# main.net
KiCad netlist of a schematic drawn in EAGLE
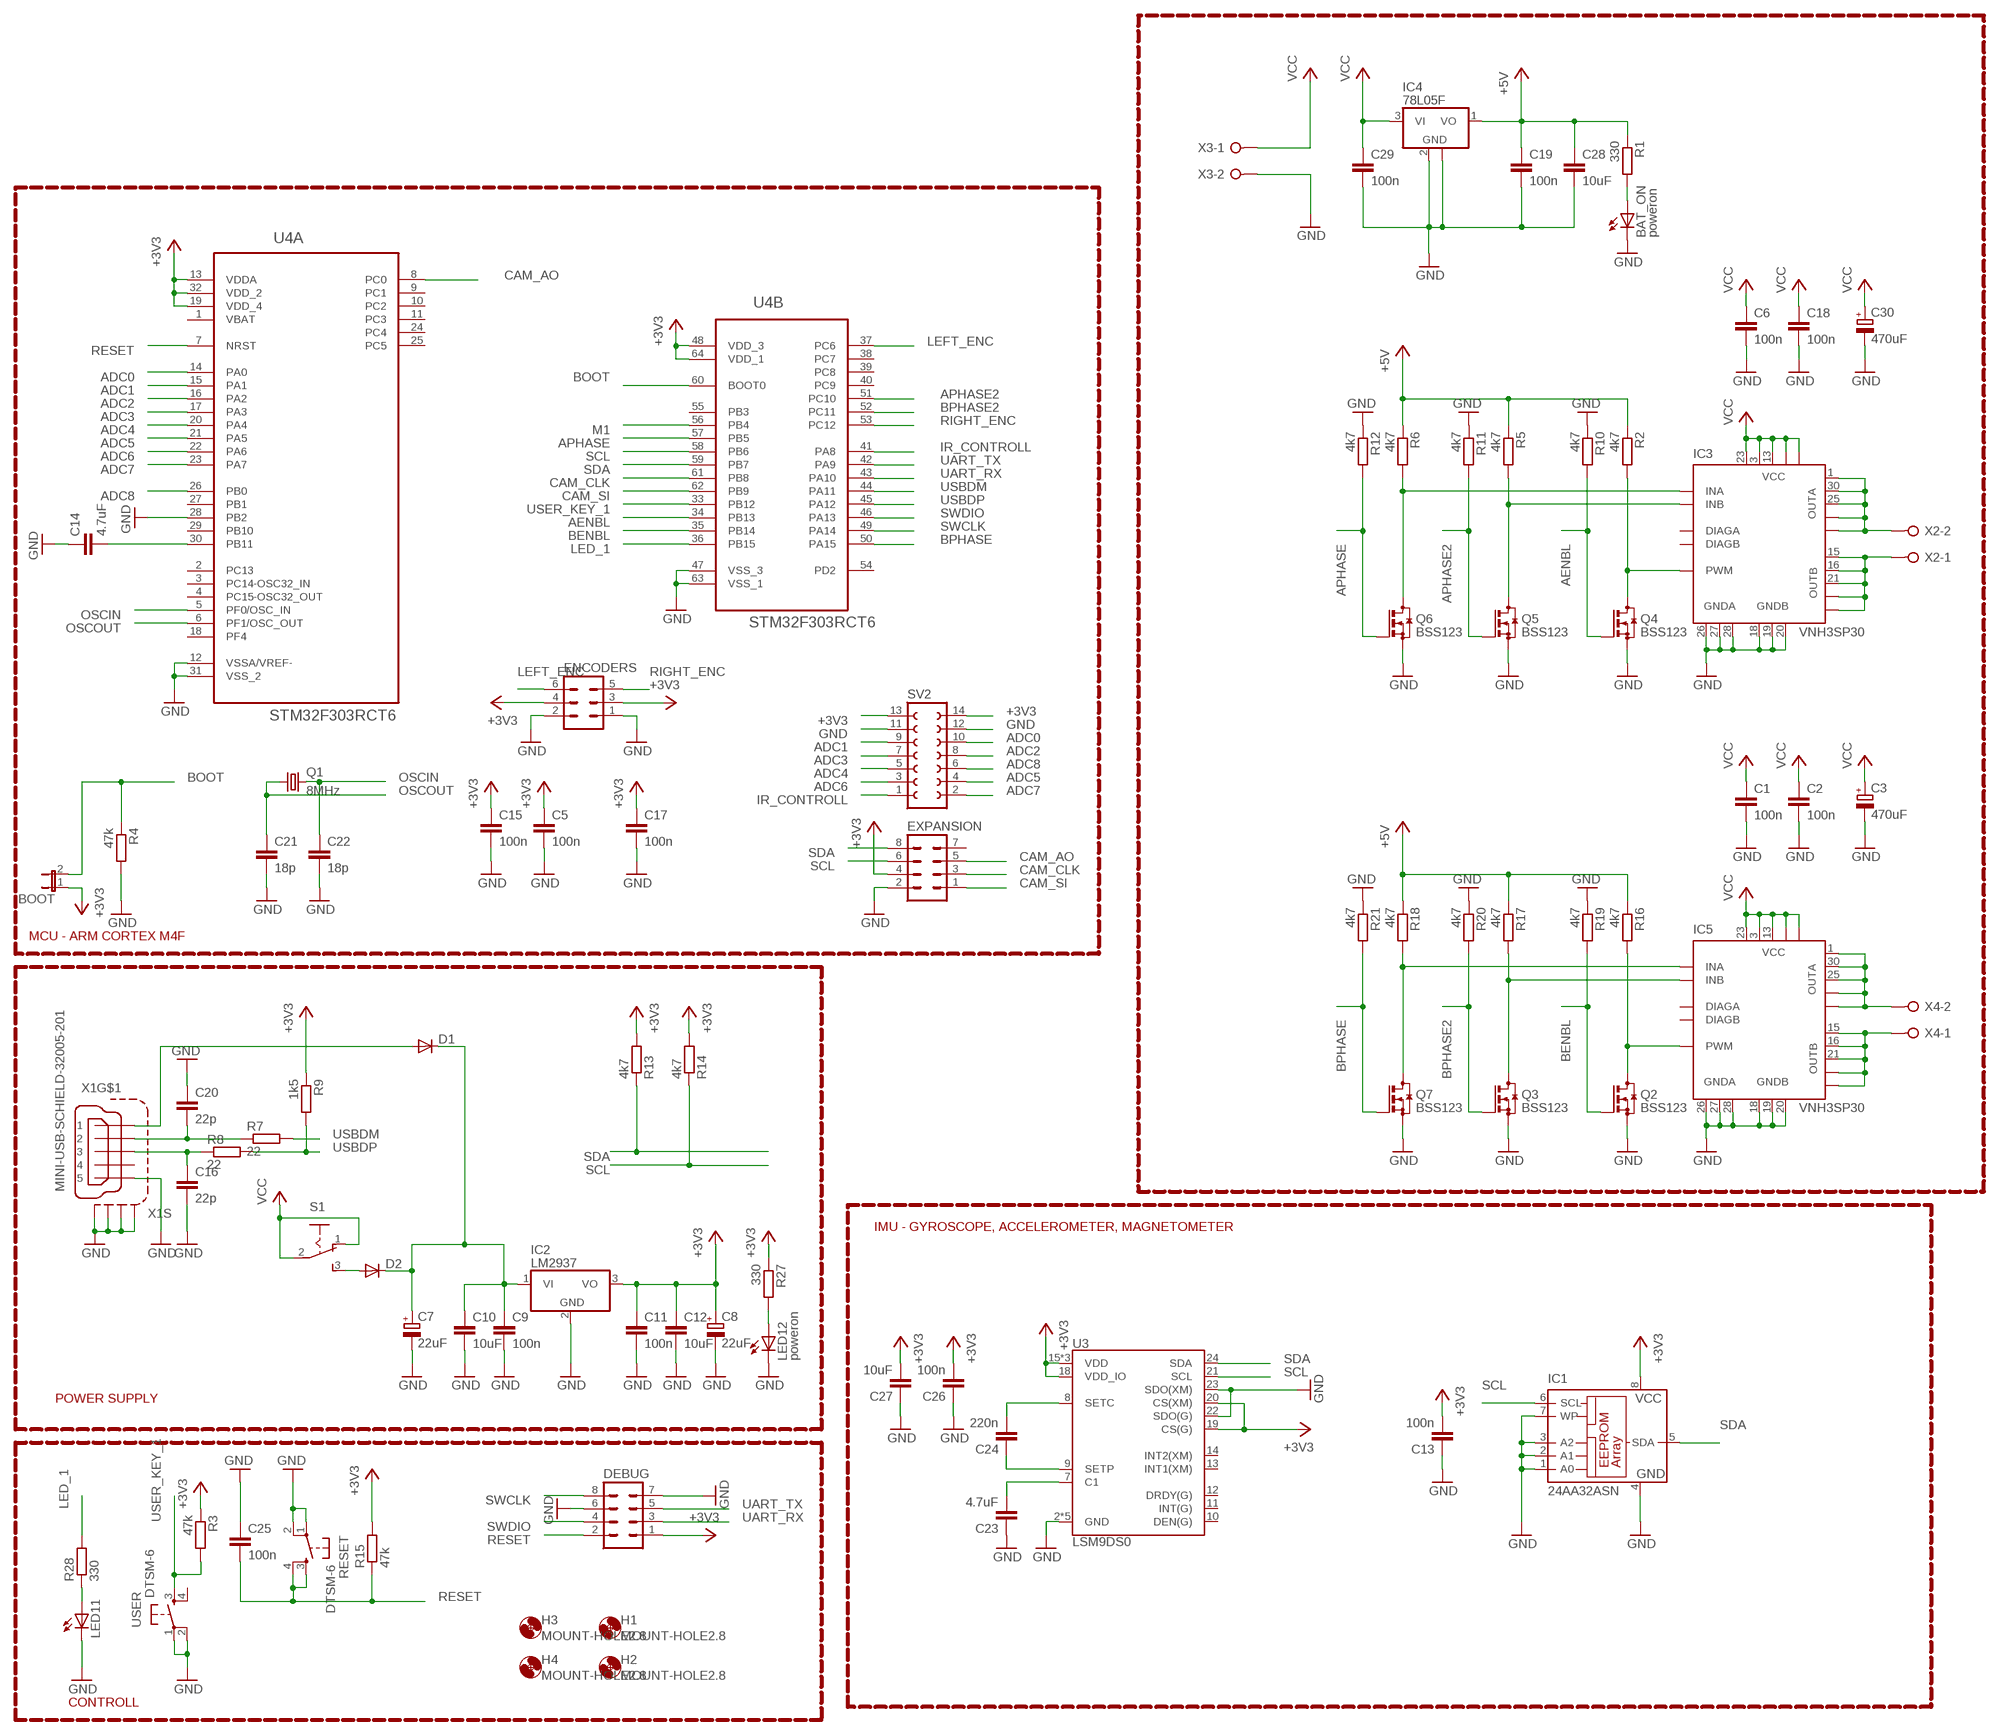
[diagram p0: schematic, sheet 1]

(export (version "E")
  (design (tool "Eeschema 10.0.6"))
  (components
    (comp (ref "BAT_ON")
      (value "poweron")
      (footprint "eagle-import:CHIPLED_1206")
      (libsource (lib "eagle-import") (part "LEDCHIPLED_1206"))
    )
    (comp (ref "BOOT")
      (value "JP1E")
      (footprint "eagle-import:JP1")
      (libsource (lib "eagle-import") (part "JP1E"))
    )
    (comp (ref "C1")
      (value "100n")
      (footprint "eagle-import:C0805")
      (libsource (lib "eagle-import") (part "C-EUC0805"))
    )
    (comp (ref "C2")
      (value "100n")
      (footprint "eagle-import:C0805")
      (libsource (lib "eagle-import") (part "C-EUC0805"))
    )
    (comp (ref "C3")
      (value "470uF")
      (footprint "eagle-import:140CLH-1014")
      (libsource (lib "eagle-import") (part "CPOL-EU140CLH-1014"))
    )
    (comp (ref "C5")
      (value "100n")
      (footprint "eagle-import:C0805")
      (libsource (lib "eagle-import") (part "C-EUC0805"))
    )
    (comp (ref "C6")
      (value "100n")
      (footprint "eagle-import:C0805")
      (libsource (lib "eagle-import") (part "C-EUC0805"))
    )
    (comp (ref "C7")
      (value "22uF")
      (footprint "eagle-import:153CLV-0505")
      (libsource (lib "eagle-import") (part "CPOL-EU153CLV-0505"))
    )
    (comp (ref "C8")
      (value "22uF")
      (footprint "eagle-import:153CLV-0505")
      (libsource (lib "eagle-import") (part "CPOL-EU153CLV-0505"))
    )
    (comp (ref "C9")
      (value "100n")
      (footprint "eagle-import:C0805")
      (libsource (lib "eagle-import") (part "C-EUC0805"))
    )
    (comp (ref "C10")
      (value "10uF")
      (footprint "eagle-import:C0805")
      (libsource (lib "eagle-import") (part "C-EUC0805"))
    )
    (comp (ref "C11")
      (value "100n")
      (footprint "eagle-import:C0805")
      (libsource (lib "eagle-import") (part "C-EUC0805"))
    )
    (comp (ref "C12")
      (value "10uF")
      (footprint "eagle-import:C0805")
      (libsource (lib "eagle-import") (part "C-EUC0805"))
    )
    (comp (ref "C13")
      (value "100n")
      (footprint "eagle-import:C0805")
      (libsource (lib "eagle-import") (part "C-EUC0805"))
    )
    (comp (ref "C14")
      (value "4.7uF")
      (footprint "eagle-import:C0805")
      (libsource (lib "eagle-import") (part "C-EUC0805"))
    )
    (comp (ref "C15")
      (value "100n")
      (footprint "eagle-import:C0805")
      (libsource (lib "eagle-import") (part "C-EUC0805"))
    )
    (comp (ref "C16")
      (value "22p")
      (footprint "eagle-import:C0805")
      (libsource (lib "eagle-import") (part "C-EUC0805"))
    )
    (comp (ref "C17")
      (value "100n")
      (footprint "eagle-import:C0805")
      (libsource (lib "eagle-import") (part "C-EUC0805"))
    )
    (comp (ref "C18")
      (value "100n")
      (footprint "eagle-import:C0805")
      (libsource (lib "eagle-import") (part "C-EUC0805"))
    )
    (comp (ref "C19")
      (value "100n")
      (footprint "eagle-import:C0805")
      (libsource (lib "eagle-import") (part "C-EUC0805"))
    )
    (comp (ref "C20")
      (value "22p")
      (footprint "eagle-import:C0805")
      (libsource (lib "eagle-import") (part "C-EUC0805"))
    )
    (comp (ref "C21")
      (value "18p")
      (footprint "eagle-import:C0805")
      (libsource (lib "eagle-import") (part "C-EUC0805"))
    )
    (comp (ref "C22")
      (value "18p")
      (footprint "eagle-import:C0805")
      (libsource (lib "eagle-import") (part "C-EUC0805"))
    )
    (comp (ref "C23")
      (value "4.7uF")
      (footprint "eagle-import:C0805")
      (libsource (lib "eagle-import") (part "C-EUC0805"))
    )
    (comp (ref "C24")
      (value "220n")
      (footprint "eagle-import:C0805")
      (libsource (lib "eagle-import") (part "C-EUC0805"))
    )
    (comp (ref "C25")
      (value "100n")
      (footprint "eagle-import:C0805")
      (libsource (lib "eagle-import") (part "C-EUC0805"))
    )
    (comp (ref "C26")
      (value "100n")
      (footprint "eagle-import:C0805")
      (libsource (lib "eagle-import") (part "C-EUC0805"))
    )
    (comp (ref "C27")
      (value "10uF")
      (footprint "eagle-import:C0805")
      (libsource (lib "eagle-import") (part "C-EUC0805"))
    )
    (comp (ref "C28")
      (value "10uF")
      (footprint "eagle-import:C0805")
      (libsource (lib "eagle-import") (part "C-EUC0805"))
    )
    (comp (ref "C29")
      (value "100n")
      (footprint "eagle-import:C0805")
      (libsource (lib "eagle-import") (part "C-EUC0805"))
    )
    (comp (ref "C30")
      (value "470uF")
      (footprint "eagle-import:140CLH-1014")
      (libsource (lib "eagle-import") (part "CPOL-EU140CLH-1014"))
    )
    (comp (ref "D1")
      (value "DIODE-SMB")
      (footprint "eagle-import:SMB")
      (libsource (lib "eagle-import") (part "DIODE-SMB"))
    )
    (comp (ref "D2")
      (value "DIODE-SMB")
      (footprint "eagle-import:SMB")
      (libsource (lib "eagle-import") (part "DIODE-SMB"))
    )
    (comp (ref "DEBUG")
      (value "MA04-2")
      (footprint "eagle-import:MA04-2")
      (libsource (lib "eagle-import") (part "MA04-2"))
    )
    (comp (ref "ENCODERS")
      (value "MA03-2")
      (footprint "eagle-import:MA03-2")
      (libsource (lib "eagle-import") (part "MA03-2"))
    )
    (comp (ref "EXPANSION")
      (value "MA04-2")
      (footprint "eagle-import:MA04-2")
      (libsource (lib "eagle-import") (part "MA04-2"))
    )
    (comp (ref "H1")
      (value "MOUNT-HOLE2.8")
      (footprint "eagle-import:2,8")
      (libsource (lib "eagle-import") (part "MOUNT-HOLE2.8"))
    )
    (comp (ref "H2")
      (value "MOUNT-HOLE2.8")
      (footprint "eagle-import:2,8")
      (libsource (lib "eagle-import") (part "MOUNT-HOLE2.8"))
    )
    (comp (ref "H3")
      (value "MOUNT-HOLE2.8")
      (footprint "eagle-import:2,8")
      (libsource (lib "eagle-import") (part "MOUNT-HOLE2.8"))
    )
    (comp (ref "H4")
      (value "MOUNT-HOLE2.8")
      (footprint "eagle-import:2,8")
      (libsource (lib "eagle-import") (part "MOUNT-HOLE2.8"))
    )
    (comp (ref "IC1")
      (value "24AA32ASN")
      (footprint "eagle-import:SO-08")
      (fields (field (name "MF") "MICROCHIP") (field (name "MPN") "24AA32A-I/SN"))
      (libsource (lib "eagle-import") (part "24SNAA32A"))
    )
    (comp (ref "IC2")
      (value "LM2937")
      (footprint "eagle-import:TO263-3")
      (libsource (lib "eagle-import") (part "LM2937"))
    )
    (comp (ref "IC3")
      (value "VNH3SP30")
      (footprint "eagle-import:MULTIPOWERSO-30")
      (fields (field (name "MPN") "VNH3SP30-E"))
      (libsource (lib "eagle-import") (part "VNH3SP30"))
    )
    (comp (ref "IC4")
      (value "78L05F")
      (footprint "eagle-import:SOT89")
      (libsource (lib "eagle-import") (part "78LF05"))
    )
    (comp (ref "IC5")
      (value "VNH3SP30")
      (footprint "eagle-import:MULTIPOWERSO-30")
      (fields (field (name "MPN") "VNH3SP30-E"))
      (libsource (lib "eagle-import") (part "VNH3SP30"))
    )
    (comp (ref "LED11")
      (value "LEDCHIPLED_1206")
      (footprint "eagle-import:CHIPLED_1206")
      (libsource (lib "eagle-import") (part "LEDCHIPLED_1206"))
    )
    (comp (ref "LED12")
      (value "poweron")
      (footprint "eagle-import:CHIPLED_1206")
      (libsource (lib "eagle-import") (part "LEDCHIPLED_1206"))
    )
    (comp (ref "Q1")
      (value "8MHz")
      (footprint "eagle-import:CTS406")
      (libsource (lib "eagle-import") (part "CRYSTALCTS406"))
    )
    (comp (ref "Q2")
      (value "BSS123")
      (footprint "eagle-import:SOT23")
      (libsource (lib "eagle-import") (part "BSS123"))
    )
    (comp (ref "Q3")
      (value "BSS123")
      (footprint "eagle-import:SOT23")
      (libsource (lib "eagle-import") (part "BSS123"))
    )
    (comp (ref "Q4")
      (value "BSS123")
      (footprint "eagle-import:SOT23")
      (libsource (lib "eagle-import") (part "BSS123"))
    )
    (comp (ref "Q5")
      (value "BSS123")
      (footprint "eagle-import:SOT23")
      (libsource (lib "eagle-import") (part "BSS123"))
    )
    (comp (ref "Q6")
      (value "BSS123")
      (footprint "eagle-import:SOT23")
      (libsource (lib "eagle-import") (part "BSS123"))
    )
    (comp (ref "Q7")
      (value "BSS123")
      (footprint "eagle-import:SOT23")
      (libsource (lib "eagle-import") (part "BSS123"))
    )
    (comp (ref "R1")
      (value "330")
      (footprint "eagle-import:M0805")
      (libsource (lib "eagle-import") (part "R-EU_M0805"))
    )
    (comp (ref "R2")
      (value "4k7")
      (footprint "eagle-import:M0805")
      (libsource (lib "eagle-import") (part "R-EU_M0805"))
    )
    (comp (ref "R3")
      (value "47k")
      (footprint "eagle-import:M0805")
      (libsource (lib "eagle-import") (part "R-EU_M0805"))
    )
    (comp (ref "R4")
      (value "47k")
      (footprint "eagle-import:M0805")
      (libsource (lib "eagle-import") (part "R-EU_M0805"))
    )
    (comp (ref "R5")
      (value "4k7")
      (footprint "eagle-import:M0805")
      (libsource (lib "eagle-import") (part "R-EU_M0805"))
    )
    (comp (ref "R6")
      (value "4k7")
      (footprint "eagle-import:M0805")
      (libsource (lib "eagle-import") (part "R-EU_M0805"))
    )
    (comp (ref "R7")
      (value "22")
      (footprint "eagle-import:M0805")
      (libsource (lib "eagle-import") (part "R-EU_M0805"))
    )
    (comp (ref "R8")
      (value "22")
      (footprint "eagle-import:M0805")
      (libsource (lib "eagle-import") (part "R-EU_M0805"))
    )
    (comp (ref "R9")
      (value "1k5")
      (footprint "eagle-import:M0805")
      (libsource (lib "eagle-import") (part "R-EU_M0805"))
    )
    (comp (ref "R10")
      (value "4k7")
      (footprint "eagle-import:M0805")
      (libsource (lib "eagle-import") (part "R-EU_M0805"))
    )
    (comp (ref "R11")
      (value "4k7")
      (footprint "eagle-import:M0805")
      (libsource (lib "eagle-import") (part "R-EU_M0805"))
    )
    (comp (ref "R12")
      (value "4k7")
      (footprint "eagle-import:M0805")
      (libsource (lib "eagle-import") (part "R-EU_M0805"))
    )
    (comp (ref "R13")
      (value "4k7")
      (footprint "eagle-import:M0805")
      (libsource (lib "eagle-import") (part "R-EU_M0805"))
    )
    (comp (ref "R14")
      (value "4k7")
      (footprint "eagle-import:M0805")
      (libsource (lib "eagle-import") (part "R-EU_M0805"))
    )
    (comp (ref "R15")
      (value "47k")
      (footprint "eagle-import:M0805")
      (libsource (lib "eagle-import") (part "R-EU_M0805"))
    )
    (comp (ref "R16")
      (value "4k7")
      (footprint "eagle-import:M0805")
      (libsource (lib "eagle-import") (part "R-EU_M0805"))
    )
    (comp (ref "R17")
      (value "4k7")
      (footprint "eagle-import:M0805")
      (libsource (lib "eagle-import") (part "R-EU_M0805"))
    )
    (comp (ref "R18")
      (value "4k7")
      (footprint "eagle-import:M0805")
      (libsource (lib "eagle-import") (part "R-EU_M0805"))
    )
    (comp (ref "R19")
      (value "4k7")
      (footprint "eagle-import:M0805")
      (libsource (lib "eagle-import") (part "R-EU_M0805"))
    )
    (comp (ref "R20")
      (value "4k7")
      (footprint "eagle-import:M0805")
      (libsource (lib "eagle-import") (part "R-EU_M0805"))
    )
    (comp (ref "R21")
      (value "4k7")
      (footprint "eagle-import:M0805")
      (libsource (lib "eagle-import") (part "R-EU_M0805"))
    )
    (comp (ref "R27")
      (value "330")
      (footprint "eagle-import:M0805")
      (libsource (lib "eagle-import") (part "R-EU_M0805"))
    )
    (comp (ref "R28")
      (value "330")
      (footprint "eagle-import:M0805")
      (libsource (lib "eagle-import") (part "R-EU_M0805"))
    )
    (comp (ref "RESET")
      (value "DTSM-6")
      (footprint "eagle-import:DTSM-6")
      (libsource (lib "eagle-import") (part "DTSM-6"))
    )
    (comp (ref "S1")
      (value "255SB")
      (footprint "eagle-import:255SB")
      (libsource (lib "eagle-import") (part "255SB"))
    )
    (comp (ref "SV2")
      (value "FE07-2")
      (footprint "eagle-import:FE07-2")
      (libsource (lib "eagle-import") (part "FE07-2"))
    )
    (comp (ref "U3")
      (value "LSM9DS0")
      (footprint "eagle-import:LGA-24")
      (libsource (lib "eagle-import") (part "LSM9DS0"))
    )
    (comp (ref "U4")
      (value "STM32F303RCT6")
      (footprint "eagle-import:QFP50P1200X1200X160-64N")
      (libsource (lib "eagle-import") (part "STM32F303RCT6"))
    )
    (comp (ref "USER")
      (value "DTSM-6")
      (footprint "eagle-import:DTSM-6")
      (libsource (lib "eagle-import") (part "DTSM-6"))
    )
    (comp (ref "X1")
      (value "MINI-USB-SCHIELD-32005-201")
      (footprint "eagle-import:32005-201")
      (libsource (lib "eagle-import") (part "MINI-USB-SCHIELD-32005-201"))
    )
    (comp (ref "X2")
      (value "W237-02P")
      (footprint "eagle-import:W237-132")
      (libsource (lib "eagle-import") (part "W237-02P"))
    )
    (comp (ref "X3")
      (value "W237-02P")
      (footprint "eagle-import:W237-132")
      (libsource (lib "eagle-import") (part "W237-02P"))
    )
    (comp (ref "X4")
      (value "W237-02P")
      (footprint "eagle-import:W237-132")
      (libsource (lib "eagle-import") (part "W237-02P"))
    )
  )
  (nets
    (net (code "1") (name "+3V3") (class "Default")
      (node (ref "BOOT") (pin "1") (pinfunction "1_1") (pintype "passive"))
      (node (ref "C11") (pin "1") (pinfunction "1_1") (pintype "passive"))
      (node (ref "C12") (pin "1") (pinfunction "1_1") (pintype "passive"))
      (node (ref "C13") (pin "2") (pinfunction "2_2") (pintype "passive"))
      (node (ref "C15") (pin "1") (pinfunction "1_1") (pintype "passive"))
      (node (ref "C17") (pin "1") (pinfunction "1_1") (pintype "passive"))
      (node (ref "C26") (pin "2") (pinfunction "2_2") (pintype "passive"))
      (node (ref "C27") (pin "2") (pinfunction "2_2") (pintype "passive"))
      (node (ref "C5") (pin "1") (pinfunction "1_1") (pintype "passive"))
      (node (ref "C8") (pin "+") (pinfunction "+_+") (pintype "passive"))
      (node (ref "DEBUG") (pin "1") (pinfunction "1_1") (pintype "passive"))
      (node (ref "ENCODERS") (pin "3") (pinfunction "3_3") (pintype "passive"))
      (node (ref "ENCODERS") (pin "4") (pinfunction "4_4") (pintype "passive"))
      (node (ref "EXPANSION") (pin "4") (pinfunction "4_4") (pintype "passive"))
      (node (ref "IC1") (pin "8") (pinfunction "VCC_8") (pintype "power_in"))
      (node (ref "IC2") (pin "3") (pinfunction "VO_3") (pintype "passive"))
      (node (ref "R13") (pin "2") (pinfunction "2_2") (pintype "passive"))
      (node (ref "R14") (pin "2") (pinfunction "2_2") (pintype "passive"))
      (node (ref "R15") (pin "2") (pinfunction "2_2") (pintype "passive"))
      (node (ref "R27") (pin "1") (pinfunction "1_1") (pintype "passive"))
      (node (ref "R3") (pin "1") (pinfunction "1_1") (pintype "passive"))
      (node (ref "R9") (pin "1") (pinfunction "1_1") (pintype "passive"))
      (node (ref "SV2") (pin "13") (pinfunction "13_13") (pintype "passive"))
      (node (ref "SV2") (pin "14") (pinfunction "14_14") (pintype "passive"))
      (node (ref "U3") (pin "15") (pinfunction "VDD_15") (pintype "bidirectional"))
      (node (ref "U3") (pin "16") (pinfunction "VDD_16") (pintype "bidirectional"))
      (node (ref "U3") (pin "17") (pinfunction "VDD_17") (pintype "bidirectional"))
      (node (ref "U3") (pin "18") (pinfunction "VDD_IO_18") (pintype "bidirectional"))
      (node (ref "U3") (pin "19") (pinfunction "CS(G)_19") (pintype "bidirectional"))
      (node (ref "U3") (pin "20") (pinfunction "CS(XM)_20") (pintype "bidirectional"))
      (node (ref "U4") (pin "13") (pinfunction "VDDA_13") (pintype "power_in"))
      (node (ref "U4") (pin "19") (pinfunction "VDD_4_19") (pintype "power_in"))
      (node (ref "U4") (pin "32") (pinfunction "VDD_2_32") (pintype "power_in"))
      (node (ref "U4") (pin "48") (pinfunction "VDD_3_48") (pintype "power_in"))
      (node (ref "U4") (pin "64") (pinfunction "VDD_1_64") (pintype "power_in"))
    )
    (net (code "2") (name "+5V") (class "Default")
      (node (ref "C19") (pin "1") (pinfunction "1_1") (pintype "passive"))
      (node (ref "C28") (pin "1") (pinfunction "1_1") (pintype "passive"))
      (node (ref "IC4") (pin "1") (pinfunction "VO_1") (pintype "passive"))
      (node (ref "R1") (pin "1") (pinfunction "1_1") (pintype "passive"))
      (node (ref "R16") (pin "1") (pinfunction "1_1") (pintype "passive"))
      (node (ref "R17") (pin "1") (pinfunction "1_1") (pintype "passive"))
      (node (ref "R18") (pin "1") (pinfunction "1_1") (pintype "passive"))
      (node (ref "R2") (pin "1") (pinfunction "1_1") (pintype "passive"))
      (node (ref "R5") (pin "1") (pinfunction "1_1") (pintype "passive"))
      (node (ref "R6") (pin "1") (pinfunction "1_1") (pintype "passive"))
    )
    (net (code "3") (name "/ADC0") (class "Default")
      (node (ref "SV2") (pin "10") (pinfunction "10_10") (pintype "passive"))
      (node (ref "U4") (pin "14") (pinfunction "PA0_14") (pintype "bidirectional"))
    )
    (net (code "4") (name "/ADC1") (class "Default")
      (node (ref "SV2") (pin "9") (pinfunction "9_9") (pintype "passive"))
      (node (ref "U4") (pin "15") (pinfunction "PA1_15") (pintype "bidirectional"))
    )
    (net (code "5") (name "/ADC2") (class "Default")
      (node (ref "SV2") (pin "8") (pinfunction "8_8") (pintype "passive"))
      (node (ref "U4") (pin "16") (pinfunction "PA2_16") (pintype "bidirectional"))
    )
    (net (code "6") (name "/ADC3") (class "Default")
      (node (ref "SV2") (pin "7") (pinfunction "7_7") (pintype "passive"))
      (node (ref "U4") (pin "17") (pinfunction "PA3_17") (pintype "bidirectional"))
    )
    (net (code "7") (name "/ADC4") (class "Default")
      (node (ref "SV2") (pin "5") (pinfunction "5_5") (pintype "passive"))
      (node (ref "U4") (pin "20") (pinfunction "PA4_20") (pintype "bidirectional"))
    )
    (net (code "8") (name "/ADC5") (class "Default")
      (node (ref "SV2") (pin "4") (pinfunction "4_4") (pintype "passive"))
      (node (ref "U4") (pin "21") (pinfunction "PA5_21") (pintype "bidirectional"))
    )
    (net (code "9") (name "/ADC6") (class "Default")
      (node (ref "SV2") (pin "3") (pinfunction "3_3") (pintype "passive"))
      (node (ref "U4") (pin "22") (pinfunction "PA6_22") (pintype "bidirectional"))
    )
    (net (code "10") (name "/ADC7") (class "Default")
      (node (ref "SV2") (pin "2") (pinfunction "2_2") (pintype "passive"))
      (node (ref "U4") (pin "23") (pinfunction "PA7_23") (pintype "bidirectional"))
    )
    (net (code "11") (name "/ADC8") (class "Default")
      (node (ref "SV2") (pin "6") (pinfunction "6_6") (pintype "passive"))
      (node (ref "U4") (pin "26") (pinfunction "PB0_26") (pintype "bidirectional"))
    )
    (net (code "12") (name "/AENBL") (class "Default")
      (node (ref "Q4") (pin "1") (pinfunction "G_1") (pintype "passive"))
      (node (ref "R10") (pin "2") (pinfunction "2_2") (pintype "passive"))
      (node (ref "U4") (pin "34") (pinfunction "PB13_34") (pintype "bidirectional"))
    )
    (net (code "13") (name "/APHASE") (class "Default")
      (node (ref "Q6") (pin "1") (pinfunction "G_1") (pintype "passive"))
      (node (ref "R12") (pin "2") (pinfunction "2_2") (pintype "passive"))
      (node (ref "U4") (pin "57") (pinfunction "PB5_57") (pintype "bidirectional"))
    )
    (net (code "14") (name "/APHASE2") (class "Default")
      (node (ref "Q5") (pin "1") (pinfunction "G_1") (pintype "passive"))
      (node (ref "R11") (pin "2") (pinfunction "2_2") (pintype "passive"))
      (node (ref "U4") (pin "51") (pinfunction "PC10_51") (pintype "bidirectional"))
    )
    (net (code "15") (name "/BENBL") (class "Default")
      (node (ref "Q2") (pin "1") (pinfunction "G_1") (pintype "passive"))
      (node (ref "R19") (pin "2") (pinfunction "2_2") (pintype "passive"))
      (node (ref "U4") (pin "35") (pinfunction "PB14_35") (pintype "bidirectional"))
    )
    (net (code "16") (name "/BOOT") (class "Default")
      (node (ref "BOOT") (pin "2") (pinfunction "2_2") (pintype "passive"))
      (node (ref "R4") (pin "1") (pinfunction "1_1") (pintype "passive"))
      (node (ref "U4") (pin "60") (pinfunction "BOOT0_60") (pintype "input"))
    )
    (net (code "17") (name "/BPHASE") (class "Default")
      (node (ref "Q7") (pin "1") (pinfunction "G_1") (pintype "passive"))
      (node (ref "R21") (pin "2") (pinfunction "2_2") (pintype "passive"))
      (node (ref "U4") (pin "50") (pinfunction "PA15_50") (pintype "bidirectional"))
    )
    (net (code "18") (name "/BPHASE2") (class "Default")
      (node (ref "Q3") (pin "1") (pinfunction "G_1") (pintype "passive"))
      (node (ref "R20") (pin "2") (pinfunction "2_2") (pintype "passive"))
      (node (ref "U4") (pin "52") (pinfunction "PC11_52") (pintype "bidirectional"))
    )
    (net (code "19") (name "/CAM_AO") (class "Default")
      (node (ref "EXPANSION") (pin "5") (pinfunction "5_5") (pintype "passive"))
      (node (ref "U4") (pin "8") (pinfunction "PC0_8") (pintype "bidirectional"))
    )
    (net (code "20") (name "/CAM_CLK") (class "Default")
      (node (ref "EXPANSION") (pin "3") (pinfunction "3_3") (pintype "passive"))
      (node (ref "U4") (pin "61") (pinfunction "PB8_61") (pintype "bidirectional"))
    )
    (net (code "21") (name "/CAM_SI") (class "Default")
      (node (ref "EXPANSION") (pin "1") (pinfunction "1_1") (pintype "passive"))
      (node (ref "U4") (pin "62") (pinfunction "PB9_62") (pintype "bidirectional"))
    )
    (net (code "22") (name "/IR_CONTROLL") (class "Default")
      (node (ref "SV2") (pin "1") (pinfunction "1_1") (pintype "passive"))
      (node (ref "U4") (pin "41") (pinfunction "PA8_41") (pintype "bidirectional"))
    )
    (net (code "23") (name "/LED_1") (class "Default")
      (node (ref "R28") (pin "2") (pinfunction "2_2") (pintype "passive"))
      (node (ref "U4") (pin "36") (pinfunction "PB15_36") (pintype "bidirectional"))
    )
    (net (code "24") (name "/LEFT_ENC") (class "Default")
      (node (ref "ENCODERS") (pin "6") (pinfunction "6_6") (pintype "passive"))
      (node (ref "U4") (pin "37") (pinfunction "PC6_37") (pintype "bidirectional"))
    )
    (net (code "25") (name "/M1") (class "Default")
      (node (ref "U4") (pin "56") (pinfunction "PB4_56") (pintype "bidirectional"))
    )
    (net (code "26") (name "/OSCIN") (class "Default")
      (node (ref "C22") (pin "1") (pinfunction "1_1") (pintype "passive"))
      (node (ref "Q1") (pin "3") (pinfunction "2_3") (pintype "passive"))
      (node (ref "U4") (pin "5") (pinfunction "PF0/OSC_IN_5") (pintype "bidirectional"))
    )
    (net (code "27") (name "/OSCOUT") (class "Default")
      (node (ref "C21") (pin "1") (pinfunction "1_1") (pintype "passive"))
      (node (ref "Q1") (pin "1") (pinfunction "1_1") (pintype "passive"))
      (node (ref "U4") (pin "6") (pinfunction "PF1/OSC_OUT_6") (pintype "bidirectional"))
    )
    (net (code "28") (name "/RESET") (class "Default")
      (node (ref "C25") (pin "2") (pinfunction "2_2") (pintype "passive"))
      (node (ref "DEBUG") (pin "2") (pinfunction "2_2") (pintype "passive"))
      (node (ref "R15") (pin "1") (pinfunction "1_1") (pintype "passive"))
      (node (ref "RESET") (pin "3") (pinfunction "3_3") (pintype "passive"))
      (node (ref "RESET") (pin "4") (pinfunction "4_4") (pintype "passive"))
      (node (ref "U4") (pin "7") (pinfunction "NRST_7") (pintype "bidirectional"))
    )
    (net (code "29") (name "/RIGHT_ENC") (class "Default")
      (node (ref "ENCODERS") (pin "5") (pinfunction "5_5") (pintype "passive"))
      (node (ref "U4") (pin "53") (pinfunction "PC12_53") (pintype "bidirectional"))
    )
    (net (code "30") (name "/SCL") (class "Default")
      (node (ref "EXPANSION") (pin "6") (pinfunction "6_6") (pintype "passive"))
      (node (ref "IC1") (pin "6") (pinfunction "SCL_6") (pintype "input"))
      (node (ref "R14") (pin "1") (pinfunction "1_1") (pintype "passive"))
      (node (ref "U3") (pin "21") (pinfunction "SCL_21") (pintype "bidirectional"))
      (node (ref "U4") (pin "58") (pinfunction "PB6_58") (pintype "bidirectional"))
    )
    (net (code "31") (name "/SDA") (class "Default")
      (node (ref "EXPANSION") (pin "8") (pinfunction "8_8") (pintype "passive"))
      (node (ref "IC1") (pin "5") (pinfunction "SDA_5") (pintype "bidirectional"))
      (node (ref "R13") (pin "1") (pinfunction "1_1") (pintype "passive"))
      (node (ref "U3") (pin "24") (pinfunction "SDA_24") (pintype "bidirectional"))
      (node (ref "U4") (pin "59") (pinfunction "PB7_59") (pintype "bidirectional"))
    )
    (net (code "32") (name "/SWCLK") (class "Default")
      (node (ref "DEBUG") (pin "8") (pinfunction "8_8") (pintype "passive"))
      (node (ref "U4") (pin "49") (pinfunction "PA14_49") (pintype "bidirectional"))
    )
    (net (code "33") (name "/SWDIO") (class "Default")
      (node (ref "DEBUG") (pin "4") (pinfunction "4_4") (pintype "passive"))
      (node (ref "U4") (pin "46") (pinfunction "PA13_46") (pintype "bidirectional"))
    )
    (net (code "34") (name "/UART_RX") (class "Default")
      (node (ref "DEBUG") (pin "3") (pinfunction "3_3") (pintype "passive"))
      (node (ref "U4") (pin "43") (pinfunction "PA10_43") (pintype "bidirectional"))
    )
    (net (code "35") (name "/UART_TX") (class "Default")
      (node (ref "DEBUG") (pin "5") (pinfunction "5_5") (pintype "passive"))
      (node (ref "U4") (pin "42") (pinfunction "PA9_42") (pintype "bidirectional"))
    )
    (net (code "36") (name "/USBDM") (class "Default")
      (node (ref "R7") (pin "2") (pinfunction "2_2") (pintype "passive"))
      (node (ref "U4") (pin "44") (pinfunction "PA11_44") (pintype "bidirectional"))
    )
    (net (code "37") (name "/USBDP") (class "Default")
      (node (ref "R8") (pin "2") (pinfunction "2_2") (pintype "passive"))
      (node (ref "R9") (pin "2") (pinfunction "2_2") (pintype "passive"))
      (node (ref "U4") (pin "45") (pinfunction "PA12_45") (pintype "bidirectional"))
    )
    (net (code "38") (name "/USER_KEY_1") (class "Default")
      (node (ref "R3") (pin "2") (pinfunction "2_2") (pintype "passive"))
      (node (ref "U4") (pin "33") (pinfunction "PB12_33") (pintype "bidirectional"))
      (node (ref "USER") (pin "3") (pinfunction "3_3") (pintype "passive"))
    )
    (net (code "39") (name "/VBAT") (class "Default")
      (node (ref "U4") (pin "1") (pinfunction "VBAT_1") (pintype "power_in"))
    )
    (net (code "40") (name "GND") (class "Default")
      (node (ref "BAT_ON") (pin "C") (pinfunction "C_C") (pintype "passive"))
      (node (ref "C1") (pin "2") (pinfunction "2_2") (pintype "passive"))
      (node (ref "C10") (pin "2") (pinfunction "2_2") (pintype "passive"))
      (node (ref "C11") (pin "2") (pinfunction "2_2") (pintype "passive"))
      (node (ref "C12") (pin "2") (pinfunction "2_2") (pintype "passive"))
      (node (ref "C13") (pin "1") (pinfunction "1_1") (pintype "passive"))
      (node (ref "C14") (pin "1") (pinfunction "1_1") (pintype "passive"))
      (node (ref "C15") (pin "2") (pinfunction "2_2") (pintype "passive"))
      (node (ref "C16") (pin "2") (pinfunction "2_2") (pintype "passive"))
      (node (ref "C17") (pin "2") (pinfunction "2_2") (pintype "passive"))
      (node (ref "C18") (pin "2") (pinfunction "2_2") (pintype "passive"))
      (node (ref "C19") (pin "2") (pinfunction "2_2") (pintype "passive"))
      (node (ref "C2") (pin "2") (pinfunction "2_2") (pintype "passive"))
      (node (ref "C20") (pin "1") (pinfunction "1_1") (pintype "passive"))
      (node (ref "C21") (pin "2") (pinfunction "2_2") (pintype "passive"))
      (node (ref "C22") (pin "2") (pinfunction "2_2") (pintype "passive"))
      (node (ref "C23") (pin "1") (pinfunction "1_1") (pintype "passive"))
      (node (ref "C25") (pin "1") (pinfunction "1_1") (pintype "passive"))
      (node (ref "C26") (pin "1") (pinfunction "1_1") (pintype "passive"))
      (node (ref "C27") (pin "1") (pinfunction "1_1") (pintype "passive"))
      (node (ref "C28") (pin "2") (pinfunction "2_2") (pintype "passive"))
      (node (ref "C29") (pin "2") (pinfunction "2_2") (pintype "passive"))
      (node (ref "C3") (pin "-") (pinfunction "-_-") (pintype "passive"))
      (node (ref "C30") (pin "-") (pinfunction "-_-") (pintype "passive"))
      (node (ref "C5") (pin "2") (pinfunction "2_2") (pintype "passive"))
      (node (ref "C6") (pin "2") (pinfunction "2_2") (pintype "passive"))
      (node (ref "C7") (pin "-") (pinfunction "-_-") (pintype "passive"))
      (node (ref "C8") (pin "-") (pinfunction "-_-") (pintype "passive"))
      (node (ref "C9") (pin "2") (pinfunction "2_2") (pintype "passive"))
      (node (ref "DEBUG") (pin "6") (pinfunction "6_6") (pintype "passive"))
      (node (ref "DEBUG") (pin "7") (pinfunction "7_7") (pintype "passive"))
      (node (ref "ENCODERS") (pin "1") (pinfunction "1_1") (pintype "passive"))
      (node (ref "ENCODERS") (pin "2") (pinfunction "2_2") (pintype "passive"))
      (node (ref "EXPANSION") (pin "2") (pinfunction "2_2") (pintype "passive"))
      (node (ref "IC1") (pin "1") (pinfunction "A0_1") (pintype "input"))
      (node (ref "IC1") (pin "2") (pinfunction "A1_2") (pintype "input"))
      (node (ref "IC1") (pin "3") (pinfunction "A2_3") (pintype "input"))
      (node (ref "IC1") (pin "4") (pinfunction "GND_4") (pintype "power_in"))
      (node (ref "IC1") (pin "7") (pinfunction "WP_7") (pintype "input"))
      (node (ref "IC2") (pin "2") (pinfunction "GND_2") (pintype "passive"))
      (node (ref "IC3") (pin "18") (pinfunction "GNDB_18") (pintype "power_in"))
      (node (ref "IC3") (pin "19") (pinfunction "GNDB_19") (pintype "power_in"))
      (node (ref "IC3") (pin "20") (pinfunction "GNDB_20") (pintype "power_in"))
      (node (ref "IC3") (pin "26") (pinfunction "GNDA_26") (pintype "power_in"))
      (node (ref "IC3") (pin "27") (pinfunction "GNDA_27") (pintype "power_in"))
      (node (ref "IC3") (pin "28") (pinfunction "GNDA_28") (pintype "power_in"))
      (node (ref "IC4") (pin "2") (pinfunction "GND_2") (pintype "passive"))
      (node (ref "IC4") (pin "2@1") (pinfunction "GND_2@1") (pintype "passive"))
      (node (ref "IC5") (pin "18") (pinfunction "GNDB_18") (pintype "power_in"))
      (node (ref "IC5") (pin "19") (pinfunction "GNDB_19") (pintype "power_in"))
      (node (ref "IC5") (pin "20") (pinfunction "GNDB_20") (pintype "power_in"))
      (node (ref "IC5") (pin "26") (pinfunction "GNDA_26") (pintype "power_in"))
      (node (ref "IC5") (pin "27") (pinfunction "GNDA_27") (pintype "power_in"))
      (node (ref "IC5") (pin "28") (pinfunction "GNDA_28") (pintype "power_in"))
      (node (ref "LED11") (pin "C") (pinfunction "C_C") (pintype "passive"))
      (node (ref "LED12") (pin "C") (pinfunction "C_C") (pintype "passive"))
      (node (ref "Q2") (pin "2") (pinfunction "S_2") (pintype "passive"))
      (node (ref "Q3") (pin "2") (pinfunction "S_2") (pintype "passive"))
      (node (ref "Q4") (pin "2") (pinfunction "S_2") (pintype "passive"))
      (node (ref "Q5") (pin "2") (pinfunction "S_2") (pintype "passive"))
      (node (ref "Q6") (pin "2") (pinfunction "S_2") (pintype "passive"))
      (node (ref "Q7") (pin "2") (pinfunction "S_2") (pintype "passive"))
      (node (ref "R10") (pin "1") (pinfunction "1_1") (pintype "passive"))
      (node (ref "R11") (pin "1") (pinfunction "1_1") (pintype "passive"))
      (node (ref "R12") (pin "1") (pinfunction "1_1") (pintype "passive"))
      (node (ref "R19") (pin "1") (pinfunction "1_1") (pintype "passive"))
      (node (ref "R20") (pin "1") (pinfunction "1_1") (pintype "passive"))
      (node (ref "R21") (pin "1") (pinfunction "1_1") (pintype "passive"))
      (node (ref "R4") (pin "2") (pinfunction "2_2") (pintype "passive"))
      (node (ref "RESET") (pin "1") (pinfunction "1_1") (pintype "passive"))
      (node (ref "RESET") (pin "2") (pinfunction "2_2") (pintype "passive"))
      (node (ref "SV2") (pin "11") (pinfunction "11_11") (pintype "passive"))
      (node (ref "SV2") (pin "12") (pinfunction "12_12") (pintype "passive"))
      (node (ref "U3") (pin "2") (pinfunction "GND_2") (pintype "bidirectional"))
      (node (ref "U3") (pin "22") (pinfunction "SDO(G)_22") (pintype "bidirectional"))
      (node (ref "U3") (pin "23") (pinfunction "SDO(XM)_23") (pintype "bidirectional"))
      (node (ref "U3") (pin "3") (pinfunction "GND_3") (pintype "bidirectional"))
      (node (ref "U3") (pin "4") (pinfunction "GND_4") (pintype "bidirectional"))
      (node (ref "U3") (pin "5") (pinfunction "GND_5") (pintype "bidirectional"))
      (node (ref "U3") (pin "6") (pinfunction "GND_6") (pintype "bidirectional"))
      (node (ref "U4") (pin "12") (pinfunction "VSSA/VREF-_12") (pintype "power_in"))
      (node (ref "U4") (pin "28") (pinfunction "PB2_28") (pintype "bidirectional"))
      (node (ref "U4") (pin "31") (pinfunction "VSS_2_31") (pintype "passive"))
      (node (ref "U4") (pin "47") (pinfunction "VSS_3_47") (pintype "passive"))
      (node (ref "U4") (pin "63") (pinfunction "VSS_1_63") (pintype "passive"))
      (node (ref "USER") (pin "1") (pinfunction "1_1") (pintype "passive"))
      (node (ref "USER") (pin "2") (pinfunction "2_2") (pintype "passive"))
      (node (ref "X1") (pin "5") (pinfunction "5_5") (pintype "passive"))
      (node (ref "X1") (pin "M1") (pinfunction "S1_M1") (pintype "passive"))
      (node (ref "X1") (pin "M2") (pinfunction "S2_M2") (pintype "passive"))
      (node (ref "X1") (pin "M3") (pinfunction "S3_M3") (pintype "passive"))
      (node (ref "X1") (pin "M4") (pinfunction "S4_M4") (pintype "passive"))
      (node (ref "X3") (pin "2") (pinfunction "KL_2") (pintype "passive"))
    )
    (net (code "41") (name "Net-(BAT_ON-PadA)") (class "Default")
      (node (ref "BAT_ON") (pin "A") (pinfunction "A_A") (pintype "passive"))
      (node (ref "R1") (pin "2") (pinfunction "2_2") (pintype "passive"))
    )
    (net (code "42") (name "Net-(C16-Pad1)") (class "Default")
      (node (ref "C16") (pin "1") (pinfunction "1_1") (pintype "passive"))
      (node (ref "R8") (pin "1") (pinfunction "1_1") (pintype "passive"))
      (node (ref "X1") (pin "3") (pinfunction "3_3") (pintype "passive"))
    )
    (net (code "43") (name "Net-(C20-Pad2)") (class "Default")
      (node (ref "C20") (pin "2") (pinfunction "2_2") (pintype "passive"))
      (node (ref "R7") (pin "1") (pinfunction "1_1") (pintype "passive"))
      (node (ref "X1") (pin "2") (pinfunction "2_2") (pintype "passive"))
    )
    (net (code "44") (name "Net-(D1-PadA)") (class "Default")
      (node (ref "D1") (pin "A") (pinfunction "A_A") (pintype "passive"))
      (node (ref "X1") (pin "1") (pinfunction "1_1") (pintype "passive"))
    )
    (net (code "45") (name "Net-(IC2-VI)") (class "Default")
      (node (ref "C10") (pin "1") (pinfunction "1_1") (pintype "passive"))
      (node (ref "C7") (pin "+") (pinfunction "+_+") (pintype "passive"))
      (node (ref "C9") (pin "1") (pinfunction "1_1") (pintype "passive"))
      (node (ref "D1") (pin "C") (pinfunction "C_C") (pintype "passive"))
      (node (ref "D2") (pin "C") (pinfunction "C_C") (pintype "passive"))
      (node (ref "IC2") (pin "1") (pinfunction "VI_1") (pintype "input"))
    )
    (net (code "46") (name "Net-(IC3-INA)") (class "Default")
      (node (ref "IC3") (pin "5") (pinfunction "INA_5") (pintype "input"))
      (node (ref "Q6") (pin "3") (pinfunction "D_3") (pintype "passive"))
      (node (ref "R6") (pin "2") (pinfunction "2_2") (pintype "passive"))
    )
    (net (code "47") (name "Net-(IC3-INB)") (class "Default")
      (node (ref "IC3") (pin "11") (pinfunction "INB_11") (pintype "input"))
      (node (ref "Q5") (pin "3") (pinfunction "D_3") (pintype "passive"))
      (node (ref "R5") (pin "2") (pinfunction "2_2") (pintype "passive"))
    )
    (net (code "48") (name "Net-(IC3-PWM)") (class "Default")
      (node (ref "IC3") (pin "8") (pinfunction "PWM_8") (pintype "input"))
      (node (ref "Q4") (pin "3") (pinfunction "D_3") (pintype "passive"))
      (node (ref "R2") (pin "2") (pinfunction "2_2") (pintype "passive"))
    )
    (net (code "49") (name "Net-(IC5-INA)") (class "Default")
      (node (ref "IC5") (pin "5") (pinfunction "INA_5") (pintype "input"))
      (node (ref "Q7") (pin "3") (pinfunction "D_3") (pintype "passive"))
      (node (ref "R18") (pin "2") (pinfunction "2_2") (pintype "passive"))
    )
    (net (code "50") (name "Net-(IC5-INB)") (class "Default")
      (node (ref "IC5") (pin "11") (pinfunction "INB_11") (pintype "input"))
      (node (ref "Q3") (pin "3") (pinfunction "D_3") (pintype "passive"))
      (node (ref "R17") (pin "2") (pinfunction "2_2") (pintype "passive"))
    )
    (net (code "51") (name "Net-(IC5-PWM)") (class "Default")
      (node (ref "IC5") (pin "8") (pinfunction "PWM_8") (pintype "input"))
      (node (ref "Q2") (pin "3") (pinfunction "D_3") (pintype "passive"))
      (node (ref "R16") (pin "2") (pinfunction "2_2") (pintype "passive"))
    )
    (net (code "52") (name "Net-(LED11-PadA)") (class "Default")
      (node (ref "LED11") (pin "A") (pinfunction "A_A") (pintype "passive"))
      (node (ref "R28") (pin "1") (pinfunction "1_1") (pintype "passive"))
    )
    (net (code "53") (name "Net-(LED12-PadA)") (class "Default")
      (node (ref "LED12") (pin "A") (pinfunction "A_A") (pintype "passive"))
      (node (ref "R27") (pin "2") (pinfunction "2_2") (pintype "passive"))
    )
    (net (code "54") (name "Net-(S1-S)") (class "Default")
      (node (ref "D2") (pin "A") (pinfunction "A_A") (pintype "passive"))
      (node (ref "S1") (pin "3") (pinfunction "S_3") (pintype "passive"))
    )
    (net (code "55") (name "Net-(U3-C1)") (class "Default")
      (node (ref "C23") (pin "2") (pinfunction "2_2") (pintype "passive"))
      (node (ref "U3") (pin "7") (pinfunction "C1_7") (pintype "bidirectional"))
    )
    (net (code "56") (name "Net-(U3-SETC)") (class "Default")
      (node (ref "C24") (pin "2") (pinfunction "2_2") (pintype "passive"))
      (node (ref "U3") (pin "8") (pinfunction "SETC_8") (pintype "bidirectional"))
    )
    (net (code "57") (name "Net-(U3-SETP)") (class "Default")
      (node (ref "C24") (pin "1") (pinfunction "1_1") (pintype "passive"))
      (node (ref "U3") (pin "9") (pinfunction "SETP_9") (pintype "bidirectional"))
    )
    (net (code "58") (name "Net-(U4A-PB11)") (class "Default")
      (node (ref "C14") (pin "2") (pinfunction "2_2") (pintype "passive"))
      (node (ref "U4") (pin "30") (pinfunction "PB11_30") (pintype "bidirectional"))
    )
    (net (code "59") (name "Net-(X2A-KL)") (class "Default")
      (node (ref "IC3") (pin "15") (pinfunction "OUTB_15") (pintype "output"))
      (node (ref "IC3") (pin "16") (pinfunction "OUTB_16") (pintype "passive"))
      (node (ref "IC3") (pin "21") (pinfunction "OUTB_21") (pintype "passive"))
      (node (ref "IC3") (pin "OUTB") (pinfunction "OUTB_OUTB") (pintype "passive"))
      (node (ref "IC3") (pin "OUTB@1") (pinfunction "OUTB_OUTB@1") (pintype "passive"))
      (node (ref "X2") (pin "1") (pinfunction "KL_1") (pintype "passive"))
    )
    (net (code "60") (name "Net-(X2B-KL)") (class "Default")
      (node (ref "IC3") (pin "1") (pinfunction "OUTA_1") (pintype "output"))
      (node (ref "IC3") (pin "25") (pinfunction "OUTA_25") (pintype "passive"))
      (node (ref "IC3") (pin "30") (pinfunction "OUTA_30") (pintype "passive"))
      (node (ref "IC3") (pin "OUTA") (pinfunction "OUTA_OUTA") (pintype "passive"))
      (node (ref "IC3") (pin "OUTA@1") (pinfunction "OUTA_OUTA@1") (pintype "passive"))
      (node (ref "X2") (pin "2") (pinfunction "KL_2") (pintype "passive"))
    )
    (net (code "61") (name "Net-(X4A-KL)") (class "Default")
      (node (ref "IC5") (pin "15") (pinfunction "OUTB_15") (pintype "output"))
      (node (ref "IC5") (pin "16") (pinfunction "OUTB_16") (pintype "passive"))
      (node (ref "IC5") (pin "21") (pinfunction "OUTB_21") (pintype "passive"))
      (node (ref "IC5") (pin "OUTB") (pinfunction "OUTB_OUTB") (pintype "passive"))
      (node (ref "IC5") (pin "OUTB@1") (pinfunction "OUTB_OUTB@1") (pintype "passive"))
      (node (ref "X4") (pin "1") (pinfunction "KL_1") (pintype "passive"))
    )
    (net (code "62") (name "Net-(X4B-KL)") (class "Default")
      (node (ref "IC5") (pin "1") (pinfunction "OUTA_1") (pintype "output"))
      (node (ref "IC5") (pin "25") (pinfunction "OUTA_25") (pintype "passive"))
      (node (ref "IC5") (pin "30") (pinfunction "OUTA_30") (pintype "passive"))
      (node (ref "IC5") (pin "OUTA") (pinfunction "OUTA_OUTA") (pintype "passive"))
      (node (ref "IC5") (pin "OUTA@1") (pinfunction "OUTA_OUTA@1") (pintype "passive"))
      (node (ref "X4") (pin "2") (pinfunction "KL_2") (pintype "passive"))
    )
    (net (code "63") (name "VCC") (class "Default")
      (node (ref "C1") (pin "1") (pinfunction "1_1") (pintype "passive"))
      (node (ref "C18") (pin "1") (pinfunction "1_1") (pintype "passive"))
      (node (ref "C2") (pin "1") (pinfunction "1_1") (pintype "passive"))
      (node (ref "C29") (pin "1") (pinfunction "1_1") (pintype "passive"))
      (node (ref "C3") (pin "+") (pinfunction "+_+") (pintype "passive"))
      (node (ref "C30") (pin "+") (pinfunction "+_+") (pintype "passive"))
      (node (ref "C6") (pin "1") (pinfunction "1_1") (pintype "passive"))
      (node (ref "IC3") (pin "13") (pinfunction "VCC_13") (pintype "power_in"))
      (node (ref "IC3") (pin "23") (pinfunction "VCC_23") (pintype "power_in"))
      (node (ref "IC3") (pin "3") (pinfunction "VCC_3") (pintype "power_in"))
      (node (ref "IC3") (pin "VCC") (pinfunction "VCC_VCC") (pintype "power_in"))
      (node (ref "IC3") (pin "VCC@1") (pinfunction "VCC_VCC@1") (pintype "power_in"))
      (node (ref "IC4") (pin "3") (pinfunction "VI_3") (pintype "input"))
      (node (ref "IC5") (pin "13") (pinfunction "VCC_13") (pintype "power_in"))
      (node (ref "IC5") (pin "23") (pinfunction "VCC_23") (pintype "power_in"))
      (node (ref "IC5") (pin "3") (pinfunction "VCC_3") (pintype "power_in"))
      (node (ref "IC5") (pin "VCC") (pinfunction "VCC_VCC") (pintype "power_in"))
      (node (ref "IC5") (pin "VCC@1") (pinfunction "VCC_VCC@1") (pintype "power_in"))
      (node (ref "S1") (pin "1") (pinfunction "O_1") (pintype "passive"))
      (node (ref "S1") (pin "2") (pinfunction "P_2") (pintype "passive"))
      (node (ref "X3") (pin "1") (pinfunction "KL_1") (pintype "passive"))
    )
    (net (code "64") (name "unconnected-(EXPANSION-Pad7)") (class "Default")
      (node (ref "EXPANSION") (pin "7") (pinfunction "7_7") (pintype "passive"))
    )
    (net (code "65") (name "unconnected-(IC3-DIAGA-Pad6)") (class "Default")
      (node (ref "IC3") (pin "6") (pinfunction "DIAGA_6") (pintype "open_collector"))
    )
    (net (code "66") (name "unconnected-(IC3-DIAGB-Pad10)") (class "Default")
      (node (ref "IC3") (pin "10") (pinfunction "DIAGB_10") (pintype "open_collector"))
    )
    (net (code "67") (name "unconnected-(IC5-DIAGA-Pad6)") (class "Default")
      (node (ref "IC5") (pin "6") (pinfunction "DIAGA_6") (pintype "open_collector"))
    )
    (net (code "68") (name "unconnected-(IC5-DIAGB-Pad10)") (class "Default")
      (node (ref "IC5") (pin "10") (pinfunction "DIAGB_10") (pintype "open_collector"))
    )
    (net (code "69") (name "unconnected-(U3-DEN(G)-Pad10)") (class "Default")
      (node (ref "U3") (pin "10") (pinfunction "DEN(G)_10") (pintype "bidirectional"))
    )
    (net (code "70") (name "unconnected-(U3-DRDY(G)-Pad12)") (class "Default")
      (node (ref "U3") (pin "12") (pinfunction "DRDY(G)_12") (pintype "bidirectional"))
    )
    (net (code "71") (name "unconnected-(U3-INT(G)-Pad11)") (class "Default")
      (node (ref "U3") (pin "11") (pinfunction "INT(G)_11") (pintype "bidirectional"))
    )
    (net (code "72") (name "unconnected-(U3-INT1(XM)-Pad13)") (class "Default")
      (node (ref "U3") (pin "13") (pinfunction "INT1(XM)_13") (pintype "bidirectional"))
    )
    (net (code "73") (name "unconnected-(U3-INT2(XM)-Pad14)") (class "Default")
      (node (ref "U3") (pin "14") (pinfunction "INT2(XM)_14") (pintype "bidirectional"))
    )
    (net (code "74") (name "unconnected-(U4A-PB1-Pad27)") (class "Default")
      (node (ref "U4") (pin "27") (pinfunction "PB1_27") (pintype "bidirectional"))
    )
    (net (code "75") (name "unconnected-(U4A-PB10-Pad29)") (class "Default")
      (node (ref "U4") (pin "29") (pinfunction "PB10_29") (pintype "bidirectional"))
    )
    (net (code "76") (name "unconnected-(U4A-PC1-Pad9)") (class "Default")
      (node (ref "U4") (pin "9") (pinfunction "PC1_9") (pintype "bidirectional"))
    )
    (net (code "77") (name "unconnected-(U4A-PC2-Pad10)") (class "Default")
      (node (ref "U4") (pin "10") (pinfunction "PC2_10") (pintype "bidirectional"))
    )
    (net (code "78") (name "unconnected-(U4A-PC3-Pad11)") (class "Default")
      (node (ref "U4") (pin "11") (pinfunction "PC3_11") (pintype "bidirectional"))
    )
    (net (code "79") (name "unconnected-(U4A-PC4-Pad24)") (class "Default")
      (node (ref "U4") (pin "24") (pinfunction "PC4_24") (pintype "bidirectional"))
    )
    (net (code "80") (name "unconnected-(U4A-PC5-Pad25)") (class "Default")
      (node (ref "U4") (pin "25") (pinfunction "PC5_25") (pintype "bidirectional"))
    )
    (net (code "81") (name "unconnected-(U4A-PC13-Pad2)") (class "Default")
      (node (ref "U4") (pin "2") (pinfunction "PC13_2") (pintype "bidirectional"))
    )
    (net (code "82") (name "unconnected-(U4A-PC14-OSC32_IN-Pad3)") (class "Default")
      (node (ref "U4") (pin "3") (pinfunction "PC14-OSC32_IN_3") (pintype "bidirectional"))
    )
    (net (code "83") (name "unconnected-(U4A-PC15-OSC32_OUT-Pad4)") (class "Default")
      (node (ref "U4") (pin "4") (pinfunction "PC15-OSC32_OUT_4") (pintype "bidirectional"))
    )
    (net (code "84") (name "unconnected-(U4A-PF4-Pad18)") (class "Default")
      (node (ref "U4") (pin "18") (pinfunction "PF4_18") (pintype "bidirectional"))
    )
    (net (code "85") (name "unconnected-(U4B-PB3-Pad55)") (class "Default")
      (node (ref "U4") (pin "55") (pinfunction "PB3_55") (pintype "bidirectional"))
    )
    (net (code "86") (name "unconnected-(U4B-PC7-Pad38)") (class "Default")
      (node (ref "U4") (pin "38") (pinfunction "PC7_38") (pintype "bidirectional"))
    )
    (net (code "87") (name "unconnected-(U4B-PC8-Pad39)") (class "Default")
      (node (ref "U4") (pin "39") (pinfunction "PC8_39") (pintype "bidirectional"))
    )
    (net (code "88") (name "unconnected-(U4B-PC9-Pad40)") (class "Default")
      (node (ref "U4") (pin "40") (pinfunction "PC9_40") (pintype "bidirectional"))
    )
    (net (code "89") (name "unconnected-(U4B-PD2-Pad54)") (class "Default")
      (node (ref "U4") (pin "54") (pinfunction "PD2_54") (pintype "bidirectional"))
    )
    (net (code "90") (name "unconnected-(USER-Pad4)") (class "Default")
      (node (ref "USER") (pin "4") (pinfunction "4_4") (pintype "passive"))
    )
    (net (code "91") (name "unconnected-(X1-Pad4)") (class "Default")
      (node (ref "X1") (pin "4") (pinfunction "4_4") (pintype "passive"))
    )
  )
)
